# baseboard.net
KiCad netlist of a schematic drawn in Altium Designer
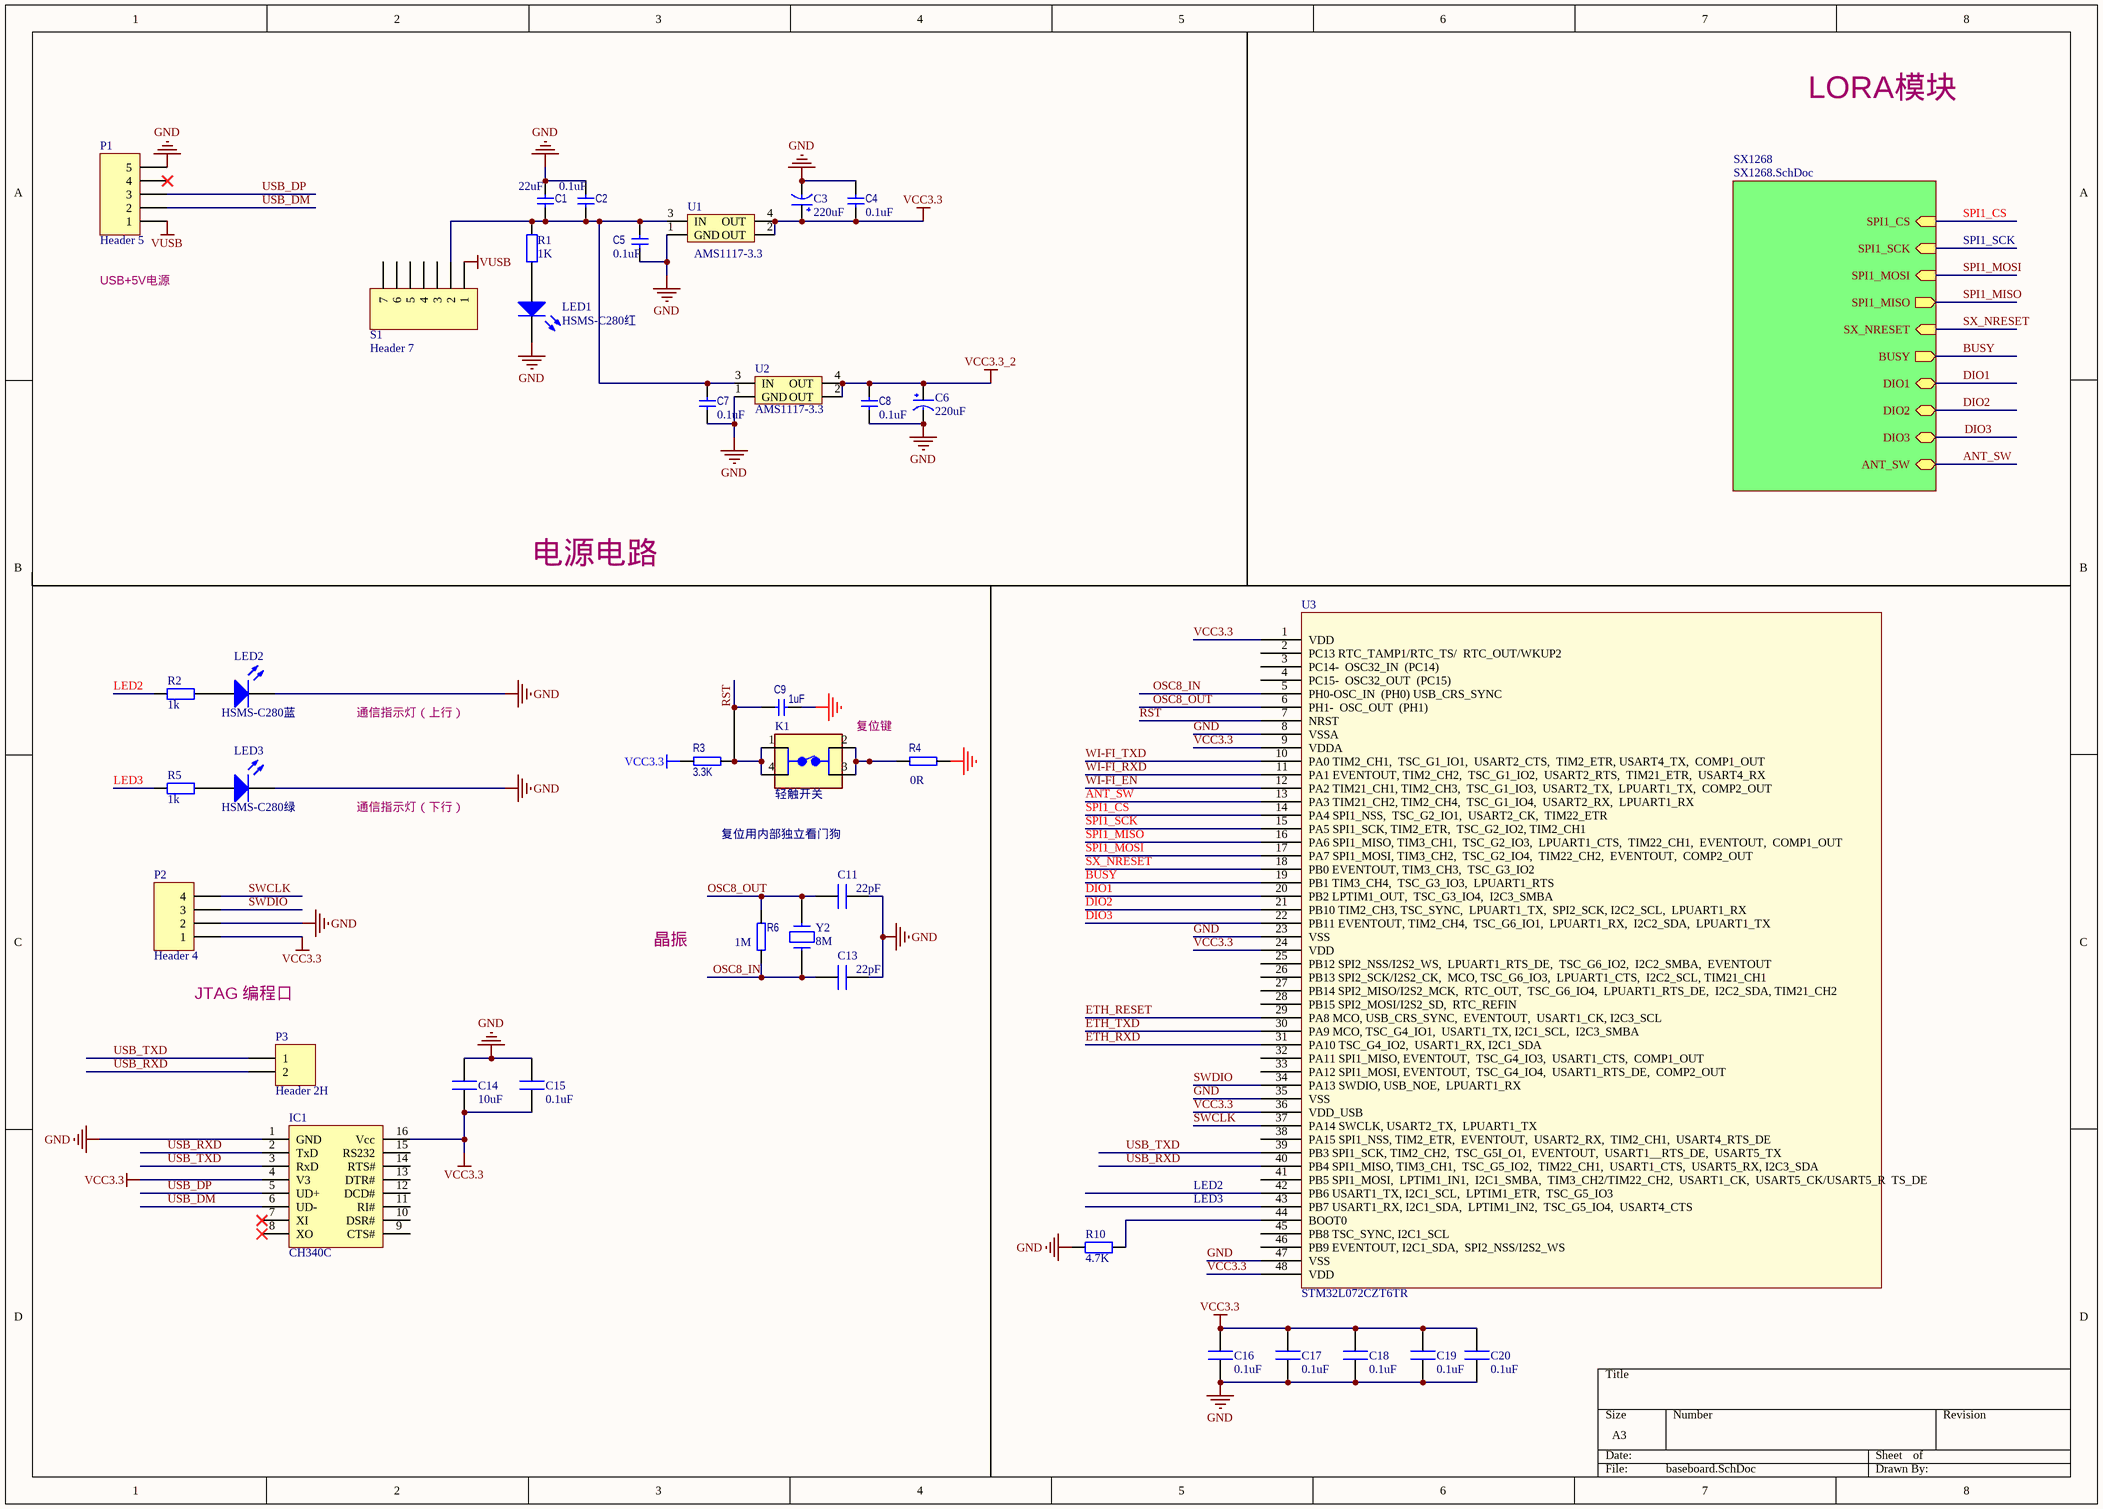
[diagram p0: baseboard.SchDoc]

(export (version "E")
  (design (tool "Eeschema 10.0.6"))
  (components
    (comp (ref "C1")
      (value "22uF")
      (footprint "C 0603_M")
      (libsource (lib "baseboard") (part "ProE.tmp_22p_13"))
    )
    (comp (ref "C2")
      (value "0.1uF")
      (footprint "C 0603_M")
      (libsource (lib "baseboard") (part "ProE.tmp_22p_13"))
    )
    (comp (ref "C3") (value "220uF") (footprint "CC6.56.5") (libsource (lib "baseboard") (part "CAP_1")))
    (comp (ref "C4")
      (value "0.1uF")
      (footprint "C 0603_M")
      (libsource (lib "baseboard") (part "ProE.tmp_22p_13"))
    )
    (comp (ref "C5")
      (value "0.1uF")
      (footprint "C 0603_M")
      (libsource (lib "baseboard") (part "ProE.tmp_22p_13"))
    )
    (comp (ref "C6") (value "220uF") (footprint "CC6.56.5") (libsource (lib "") (part "CAP_1_1")))
    (comp (ref "C7")
      (value "0.1uF")
      (footprint "C 0603_M")
      (libsource (lib "baseboard") (part "ProE.tmp_22p_13"))
    )
    (comp (ref "C8")
      (value "0.1uF")
      (footprint "C 0603_M")
      (libsource (lib "baseboard") (part "ProE.tmp_22p_13"))
    )
    (comp (ref "C9")
      (value "1uF")
      (footprint "C 0603_M")
      (libsource (lib "baseboard") (part "ProE.tmp_22p_13"))
    )
    (comp (ref "C11")
      (value "22pF")
      (footprint "C 0603_M")
      (description "Capacitor")
      (libsource (lib "Liuzhx") (part "普通贴片电容"))
    )
    (comp (ref "C13")
      (value "22pF")
      (footprint "C 0603_M")
      (description "Capacitor")
      (libsource (lib "Liuzhx") (part "普通贴片电容"))
    )
    (comp (ref "C14")
      (value "10uF")
      (footprint "C 0603_M")
      (description "Capacitor")
      (libsource (lib "Liuzhx") (part "普通贴片电容"))
    )
    (comp (ref "C15")
      (value "0.1uF")
      (footprint "C 0603_M")
      (description "Capacitor")
      (libsource (lib "Liuzhx") (part "普通贴片电容"))
    )
    (comp (ref "C16")
      (value "0.1uF")
      (footprint "C 0603_M")
      (description "Capacitor")
      (libsource (lib "Liuzhx") (part "普通贴片电容"))
    )
    (comp (ref "C17")
      (value "0.1uF")
      (footprint "C 0603_M")
      (description "Capacitor")
      (libsource (lib "Liuzhx") (part "普通贴片电容"))
    )
    (comp (ref "C18")
      (value "0.1uF")
      (footprint "C 0603_M")
      (description "Capacitor")
      (libsource (lib "Liuzhx") (part "普通贴片电容"))
    )
    (comp (ref "C19")
      (value "0.1uF")
      (footprint "C 0603_M")
      (description "Capacitor")
      (libsource (lib "Liuzhx") (part "普通贴片电容"))
    )
    (comp (ref "C20")
      (value "0.1uF")
      (footprint "C 0603_M")
      (description "Capacitor")
      (libsource (lib "Liuzhx") (part "普通贴片电容"))
    )
    (comp (ref "IC1")
      (value "CH340C")
      (footprint "SOP16_M")
      (description "串口转USB")
      (fields (field (name "版权归属") "源创客"))
      (libsource (lib "baseboard") (part "CH340G"))
    )
    (comp (ref "K1") (value "轻触开关") (footprint "SW4SM-4R5X4R5") (libsource (lib "baseboard") (part "轻触开关")))
    (comp (ref "LED1")
      (value "HSMS-C280红")
      (footprint "LED_DIP_1")
      (description "Miniature Chip LED, Red")
      (fields (field (name "PUBLISHER") "Altium Limited"))
      (libsource (lib "Agilent Optoelectronic LED") (part "HSMS-C280"))
    )
    (comp (ref "LED2")
      (value "HSMS-C280蓝")
      (footprint "LED_DIP_1")
      (description "Miniature Chip LED, Red")
      (fields (field (name "PUBLISHER") "Altium Limited"))
      (libsource (lib "Agilent Optoelectronic LED") (part "HSMS-C280"))
    )
    (comp (ref "LED3")
      (value "HSMS-C280绿")
      (footprint "LED_DIP_1")
      (description "Miniature Chip LED, Red")
      (fields (field (name "PUBLISHER") "Altium Limited"))
      (libsource (lib "Agilent Optoelectronic LED") (part "HSMS-C280"))
    )
    (comp (ref "P1")
      (value "Header 5")
      (footprint "USB-MICRO_D")
      (description "Header, 5-Pin")
      (fields (field (name "PUBLISHER") "Altium Limited"))
      (libsource (lib "Miscellaneous Connectors") (part "Header 5"))
    )
    (comp (ref "P2")
      (value "Header 4")
      (footprint "HDR1X4")
      (description "Header, 4-Pin")
      (fields (field (name "PUBLISHER") "Altium Limited"))
      (libsource (lib "Miscellaneous Connectors") (part "Header 4"))
    )
    (comp (ref "P3")
      (value "Header 2H")
      (footprint "HDR2.54-LI-2P")
      (description "Header, 2-Pin, Right Angle")
      (fields (field (name "PUBLISHER") "Altium Limited"))
      (libsource (lib "baseboard") (part "Header 2H"))
    )
    (comp (ref "R1")
      (value "1K")
      (footprint "0603R")
      (description "Resistor")
      (fields (field (name "PUBLISHER") "Altium Limited"))
      (libsource (lib "Miscellaneous Devices") (part "Res2"))
    )
    (comp (ref "R2")
      (value "1k")
      (footprint "0603R")
      (description "Resistor SMD - IEC symbol version")
      (libsource (lib "SX1276_e268v01a") (part "Resistor"))
    )
    (comp (ref "R3")
      (value "3.3K")
      (footprint "0603R")
      (libsource (lib "baseboard") (part "ProE.tmp_10k_66"))
    )
    (comp (ref "R4") (value "0R") (footprint "0603R") (libsource (lib "baseboard") (part "ProE.tmp_10k_66")))
    (comp (ref "R5")
      (value "1k")
      (footprint "0603R")
      (description "Resistor SMD - IEC symbol version")
      (libsource (lib "SX1276_e268v01a") (part "Resistor"))
    )
    (comp (ref "R6") (value "1M") (footprint "0603R") (libsource (lib "baseboard") (part "ProE.tmp_10k_66")))
    (comp (ref "R10")
      (value "4.7K")
      (footprint "0603R")
      (description "Resistor SMD - IEC symbol version")
      (libsource (lib "SX1276_e268v01a") (part "Resistor"))
    )
    (comp (ref "S1")
      (value "Header 7")
      (footprint "7脚3档开关")
      (description "Header, 7-Pin")
      (fields (field (name "PUBLISHER") "Altium Limited"))
      (libsource (lib "Miscellaneous Connectors") (part "Header 7"))
    )
    (comp (ref "U1")
      (value "AMS1117-3.3")
      (footprint "AMS1117")
      (libsource (lib "baseboard") (part "AMS1117"))
    )
    (comp (ref "U2")
      (value "AMS1117-3.3")
      (footprint "AMS1117")
      (libsource (lib "baseboard") (part "AMS1117"))
    )
    (comp (ref "U3")
      (value "STM32L072CZT6TR")
      (footprint "LQFP48_L")
      (libsource (lib "baseboard") (part "STM32L072CZT6TR"))
    )
    (comp (ref "Y2")
      (value "8M")
      (footprint "OSC3225")
      (description "Crystal")
      (libsource (lib "Liuzhx") (part "CRYSTAL"))
    )
  )
  (nets
    (net (code "1") (name "/ANT_SW") (class "Default")
      (node (ref "U3") (pin "13") (pinfunction "PA3_TIM21_CH2,_TIM2_CH4,__TSC_G1_IO4,__USART2_RX,__LPUART1_RX_13") (pintype "passive"))
    )
    (net (code "2") (name "/BUSY") (class "Default")
      (node (ref "U3") (pin "19") (pinfunction "PB1_TIM3_CH4,__TSC_G3_IO3,__LPUART1_RTS_19") (pintype "passive"))
    )
    (net (code "3") (name "/DIO1") (class "Default")
      (node (ref "U3") (pin "20") (pinfunction "PB2_LPTIM1_OUT,__TSC_G3_IO4,__I2C3_SMBA_20") (pintype "passive"))
    )
    (net (code "4") (name "/DIO2") (class "Default")
      (node (ref "U3") (pin "21") (pinfunction "PB10_TIM2_CH3,_TSC_SYNC,__LPUART1_TX,__SPI2_SCK,_I2C2_SCL,__LPUART1_RX_21") (pintype "passive"))
    )
    (net (code "5") (name "/DIO3") (class "Default")
      (node (ref "U3") (pin "22") (pinfunction "PB11_EVENTOUT,_TIM2_CH4,__TSC_G6_IO1,__LPUART1_RX,__I2C2_SDA,__LPUART1_TX_22") (pintype "passive"))
    )
    (net (code "6") (name "/ETH_RESET") (class "Default")
      (node (ref "U3") (pin "29") (pinfunction "PA8_MCO,_USB_CRS_SYNC,__EVENTOUT,__USART1_CK,_I2C3_SCL_29") (pintype "passive"))
    )
    (net (code "7") (name "/ETH_RXD") (class "Default")
      (node (ref "U3") (pin "31") (pinfunction "PA10_TSC_G4_IO2,__USART1_RX,_I2C1_SDA_31") (pintype "passive"))
    )
    (net (code "8") (name "/ETH_TXD") (class "Default")
      (node (ref "U3") (pin "30") (pinfunction "PA9_MCO,_TSC_G4_IO1,__USART1_TX,_I2C1_SCL,__I2C3_SMBA_30") (pintype "passive"))
    )
    (net (code "9") (name "/LED2") (class "Default")
      (node (ref "R2") (pin "1") (pinfunction "1_1") (pintype "passive"))
      (node (ref "U3") (pin "42") (pinfunction "PB6_USART1_TX,_I2C1_SCL,__LPTIM1_ETR,__TSC_G5_IO3_42") (pintype "passive"))
    )
    (net (code "10") (name "/LED3") (class "Default")
      (node (ref "R5") (pin "1") (pinfunction "1_1") (pintype "passive"))
      (node (ref "U3") (pin "43") (pinfunction "PB7_USART1_RX,_I2C1_SDA,__LPTIM1_IN2,__TSC_G5_IO4,__USART4_CTS_43") (pintype "passive"))
    )
    (net (code "11") (name "/OSC8_IN") (class "Default")
      (node (ref "C13") (pin "1") (pinfunction "1_1") (pintype "passive"))
      (node (ref "R6") (pin "2") (pintype "passive"))
      (node (ref "U3") (pin "5") (pinfunction "PH0-OSC_IN__(PH0)_USB_CRS_SYNC_5") (pintype "passive"))
      (node (ref "Y2") (pin "2") (pinfunction "2_2") (pintype "passive"))
    )
    (net (code "12") (name "/OSC8_OUT") (class "Default")
      (node (ref "C11") (pin "1") (pinfunction "1_1") (pintype "passive"))
      (node (ref "R6") (pin "1") (pintype "passive"))
      (node (ref "U3") (pin "6") (pinfunction "PH1-__OSC_OUT__(PH1)_6") (pintype "passive"))
      (node (ref "Y2") (pin "1") (pinfunction "1_1") (pintype "passive"))
    )
    (net (code "13") (name "/RST") (class "Default")
      (node (ref "C9") (pin "1") (pintype "passive"))
      (node (ref "K1") (pin "1") (pinfunction "1_1") (pintype "passive"))
      (node (ref "K1") (pin "4") (pinfunction "4_4") (pintype "passive"))
      (node (ref "R3") (pin "2") (pintype "passive"))
      (node (ref "U3") (pin "7") (pinfunction "NRST_7") (pintype "passive"))
    )
    (net (code "14") (name "/SPI1_CS") (class "Default")
      (node (ref "U3") (pin "14") (pinfunction "PA4_SPI1_NSS,__TSC_G2_IO1,__USART2_CK,__TIM22_ETR_14") (pintype "passive"))
    )
    (net (code "15") (name "/SPI1_MISO") (class "Default")
      (node (ref "U3") (pin "16") (pinfunction "PA6_SPI1_MISO,_TIM3_CH1,__TSC_G2_IO3,__LPUART1_CTS,__TIM22_CH1,__EVENTOUT,__COMP1_OUT_16") (pintype "passive"))
    )
    (net (code "16") (name "/SPI1_MOSI") (class "Default")
      (node (ref "U3") (pin "17") (pinfunction "PA7_SPI1_MOSI,_TIM3_CH2,__TSC_G2_IO4,__TIM22_CH2,__EVENTOUT,__COMP2_OUT_17") (pintype "passive"))
    )
    (net (code "17") (name "/SPI1_SCK") (class "Default")
      (node (ref "U3") (pin "15") (pinfunction "PA5_SPI1_SCK,_TIM2_ETR,__TSC_G2_IO2,_TIM2_CH1_15") (pintype "passive"))
    )
    (net (code "18") (name "/SWCLK") (class "Default")
      (node (ref "P2") (pin "4") (pinfunction "4_4") (pintype "passive"))
      (node (ref "U3") (pin "37") (pinfunction "PA14_SWCLK,_USART2_TX,__LPUART1_TX_37") (pintype "passive"))
    )
    (net (code "19") (name "/SWDIO") (class "Default")
      (node (ref "P2") (pin "3") (pinfunction "3_3") (pintype "passive"))
      (node (ref "U3") (pin "34") (pinfunction "PA13_SWDIO,_USB_NOE,__LPUART1_RX_34") (pintype "passive"))
    )
    (net (code "20") (name "/SX_NRESET") (class "Default")
      (node (ref "U3") (pin "18") (pinfunction "PB0_EVENTOUT,_TIM3_CH3,__TSC_G3_IO2_18") (pintype "passive"))
    )
    (net (code "21") (name "/USB_DM") (class "Default")
      (node (ref "IC1") (pin "6") (pinfunction "UD-_6") (pintype "passive"))
      (node (ref "P1") (pin "2") (pinfunction "2_2") (pintype "passive"))
    )
    (net (code "22") (name "/USB_DP") (class "Default")
      (node (ref "IC1") (pin "5") (pinfunction "UD+_5") (pintype "passive"))
      (node (ref "P1") (pin "3") (pinfunction "3_3") (pintype "passive"))
    )
    (net (code "23") (name "/USB_RXD") (class "Default")
      (node (ref "IC1") (pin "2") (pinfunction "TxD_2") (pintype "passive"))
      (node (ref "P3") (pin "2") (pinfunction "2_2") (pintype "passive"))
      (node (ref "U3") (pin "40") (pinfunction "PB4_SPI1_MISO,_TIM3_CH1,__TSC_G5_IO2,__TIM22_CH1,__USART1_CTS,__USART5_RX,_I2C3_SDA_40") (pintype "passive"))
    )
    (net (code "24") (name "/USB_TXD") (class "Default")
      (node (ref "IC1") (pin "3") (pinfunction "RxD_3") (pintype "passive"))
      (node (ref "P3") (pin "1") (pinfunction "1_1") (pintype "passive"))
      (node (ref "U3") (pin "39") (pinfunction "PB3_SPI1_SCK,_TIM2_CH2,__TSC_G5I_O1,__EVENTOUT,__USART1__RTS_DE,__USART5_TX_39") (pintype "passive"))
    )
    (net (code "25") (name "/WI-FI_EN") (class "Default")
      (node (ref "U3") (pin "12") (pinfunction "PA2_TIM21_CH1,_TIM2_CH3,__TSC_G1_IO3,__USART2_TX,__LPUART1_TX,__COMP2_OUT_12") (pintype "passive"))
    )
    (net (code "26") (name "/WI-FI_RXD") (class "Default")
      (node (ref "U3") (pin "11") (pinfunction "PA1_EVENTOUT,_TIM2_CH2,__TSC_G1_IO2,__USART2_RTS,__TIM21_ETR,__USART4_RX_11") (pintype "passive"))
    )
    (net (code "27") (name "/WI-FI_TXD") (class "Default")
      (node (ref "U3") (pin "10") (pinfunction "PA0_TIM2_CH1,__TSC_G1_IO1,__USART2_CTS,__TIM2_ETR,_USART4_TX,__COMP1_OUT_10") (pintype "passive"))
    )
    (net (code "28") (name "GND") (class "Default")
      (node (ref "C1") (pin "1") (pintype "passive"))
      (node (ref "C11") (pin "2") (pinfunction "2_2") (pintype "passive"))
      (node (ref "C13") (pin "2") (pinfunction "2_2") (pintype "passive"))
      (node (ref "C14") (pin "1") (pinfunction "1_1") (pintype "passive"))
      (node (ref "C15") (pin "2") (pinfunction "2_2") (pintype "passive"))
      (node (ref "C16") (pin "1") (pinfunction "1_1") (pintype "passive"))
      (node (ref "C17") (pin "1") (pinfunction "1_1") (pintype "passive"))
      (node (ref "C18") (pin "1") (pinfunction "1_1") (pintype "passive"))
      (node (ref "C19") (pin "1") (pinfunction "1_1") (pintype "passive"))
      (node (ref "C2") (pin "1") (pintype "passive"))
      (node (ref "C20") (pin "1") (pinfunction "1_1") (pintype "passive"))
      (node (ref "C3") (pin "2") (pinfunction "GND_2") (pintype "passive"))
      (node (ref "C4") (pin "2") (pintype "passive"))
      (node (ref "C5") (pin "1") (pintype "passive"))
      (node (ref "C6") (pin "2") (pinfunction "GND_2") (pintype "passive"))
      (node (ref "C7") (pin "1") (pintype "passive"))
      (node (ref "C8") (pin "2") (pintype "passive"))
      (node (ref "C9") (pin "2") (pintype "passive"))
      (node (ref "IC1") (pin "1") (pinfunction "GND_1") (pintype "passive"))
      (node (ref "LED1") (pin "2") (pinfunction "K_2") (pintype "passive"))
      (node (ref "LED2") (pin "2") (pinfunction "K_2") (pintype "passive"))
      (node (ref "LED3") (pin "2") (pinfunction "K_2") (pintype "passive"))
      (node (ref "P1") (pin "5") (pinfunction "5_5") (pintype "passive"))
      (node (ref "P2") (pin "2") (pinfunction "2_2") (pintype "passive"))
      (node (ref "R10") (pin "1") (pinfunction "1_1") (pintype "passive"))
      (node (ref "R4") (pin "2") (pintype "passive"))
      (node (ref "U1") (pin "1") (pinfunction "GND_1") (pintype "passive"))
      (node (ref "U2") (pin "1") (pinfunction "GND_1") (pintype "passive"))
      (node (ref "U3") (pin "23") (pinfunction "VSS_23") (pintype "passive"))
      (node (ref "U3") (pin "35") (pinfunction "VSS_35") (pintype "passive"))
      (node (ref "U3") (pin "47") (pinfunction "VSS_47") (pintype "passive"))
      (node (ref "U3") (pin "8") (pinfunction "VSSA_8") (pintype "passive"))
    )
    (net (code "29") (name "Net-(K1-Pad2)") (class "Default")
      (node (ref "K1") (pin "2") (pinfunction "2_2") (pintype "passive"))
      (node (ref "K1") (pin "3") (pinfunction "3_3") (pintype "passive"))
      (node (ref "R4") (pin "1") (pintype "passive"))
    )
    (net (code "30") (name "Net-(LED1-A)") (class "Default")
      (node (ref "LED1") (pin "1") (pinfunction "A_1") (pintype "passive"))
      (node (ref "R1") (pin "1") (pinfunction "1_1") (pintype "passive"))
    )
    (net (code "31") (name "Net-(LED2-A)") (class "Default")
      (node (ref "LED2") (pin "1") (pinfunction "A_1") (pintype "passive"))
      (node (ref "R2") (pin "2") (pinfunction "2_2") (pintype "passive"))
    )
    (net (code "32") (name "Net-(LED3-A)") (class "Default")
      (node (ref "LED3") (pin "1") (pinfunction "A_1") (pintype "passive"))
      (node (ref "R5") (pin "2") (pinfunction "2_2") (pintype "passive"))
    )
    (net (code "33") (name "Net-(U1-IN)") (class "Default")
      (node (ref "C1") (pin "2") (pintype "passive"))
      (node (ref "C2") (pin "2") (pintype "passive"))
      (node (ref "C5") (pin "2") (pintype "passive"))
      (node (ref "C7") (pin "2") (pintype "passive"))
      (node (ref "R1") (pin "2") (pinfunction "2_2") (pintype "passive"))
      (node (ref "S1") (pin "2") (pinfunction "2_2") (pintype "passive"))
      (node (ref "U1") (pin "3") (pinfunction "IN_3") (pintype "passive"))
      (node (ref "U2") (pin "3") (pinfunction "IN_3") (pintype "passive"))
    )
    (net (code "34") (name "Net-(U3-BOOT0)") (class "Default")
      (node (ref "R10") (pin "2") (pinfunction "2_2") (pintype "passive"))
      (node (ref "U3") (pin "44") (pinfunction "BOOT0_44") (pintype "passive"))
    )
    (net (code "35") (name "VCC3.3") (class "Default")
      (node (ref "C14") (pin "2") (pinfunction "2_2") (pintype "passive"))
      (node (ref "C15") (pin "1") (pinfunction "1_1") (pintype "passive"))
      (node (ref "C16") (pin "2") (pinfunction "2_2") (pintype "passive"))
      (node (ref "C17") (pin "2") (pinfunction "2_2") (pintype "passive"))
      (node (ref "C18") (pin "2") (pinfunction "2_2") (pintype "passive"))
      (node (ref "C19") (pin "2") (pinfunction "2_2") (pintype "passive"))
      (node (ref "C20") (pin "2") (pinfunction "2_2") (pintype "passive"))
      (node (ref "C3") (pin "1") (pinfunction "VCC_1") (pintype "passive"))
      (node (ref "C4") (pin "1") (pintype "passive"))
      (node (ref "IC1") (pin "16") (pinfunction "Vcc_16") (pintype "passive"))
      (node (ref "IC1") (pin "4") (pinfunction "V3_4") (pintype "passive"))
      (node (ref "P2") (pin "1") (pinfunction "1_1") (pintype "passive"))
      (node (ref "R3") (pin "1") (pintype "passive"))
      (node (ref "U1") (pin "2") (pinfunction "OUT_2") (pintype "passive"))
      (node (ref "U1") (pin "4") (pinfunction "OUT_4") (pintype "passive"))
      (node (ref "U3") (pin "1") (pinfunction "VDD_1") (pintype "passive"))
      (node (ref "U3") (pin "24") (pinfunction "VDD_24") (pintype "passive"))
      (node (ref "U3") (pin "36") (pinfunction "VDD_USB_36") (pintype "passive"))
      (node (ref "U3") (pin "48") (pinfunction "VDD_48") (pintype "passive"))
      (node (ref "U3") (pin "9") (pinfunction "VDDA_9") (pintype "passive"))
    )
    (net (code "36") (name "VCC3.3_2") (class "Default")
      (node (ref "C6") (pin "1") (pinfunction "VCC_1") (pintype "passive"))
      (node (ref "C8") (pin "1") (pintype "passive"))
      (node (ref "U2") (pin "2") (pinfunction "OUT_2") (pintype "passive"))
      (node (ref "U2") (pin "4") (pinfunction "OUT_4") (pintype "passive"))
    )
    (net (code "37") (name "VUSB") (class "Default")
      (node (ref "P1") (pin "1") (pinfunction "1_1") (pintype "passive"))
      (node (ref "S1") (pin "1") (pinfunction "1_1") (pintype "passive"))
    )
    (net (code "38") (name "unconnected-(IC1-CTS#-Pad9)") (class "Default")
      (node (ref "IC1") (pin "9") (pinfunction "CTS#_9") (pintype "passive"))
    )
    (net (code "39") (name "unconnected-(IC1-DCD#-Pad12)") (class "Default")
      (node (ref "IC1") (pin "12") (pinfunction "DCD#_12") (pintype "passive"))
    )
    (net (code "40") (name "unconnected-(IC1-DSR#-Pad10)") (class "Default")
      (node (ref "IC1") (pin "10") (pinfunction "DSR#_10") (pintype "passive"))
    )
    (net (code "41") (name "unconnected-(IC1-DTR#-Pad13)") (class "Default")
      (node (ref "IC1") (pin "13") (pinfunction "DTR#_13") (pintype "passive"))
    )
    (net (code "42") (name "unconnected-(IC1-RI#-Pad11)") (class "Default")
      (node (ref "IC1") (pin "11") (pinfunction "RI#_11") (pintype "passive"))
    )
    (net (code "43") (name "unconnected-(IC1-RS232-Pad15)") (class "Default")
      (node (ref "IC1") (pin "15") (pinfunction "RS232_15") (pintype "passive"))
    )
    (net (code "44") (name "unconnected-(IC1-RTS#-Pad14)") (class "Default")
      (node (ref "IC1") (pin "14") (pinfunction "RTS#_14") (pintype "passive"))
    )
    (net (code "45") (name "unconnected-(IC1-XI-Pad7)") (class "Default")
      (node (ref "IC1") (pin "7") (pinfunction "XI_7") (pintype "passive+no_connect"))
    )
    (net (code "46") (name "unconnected-(IC1-XO-Pad8)") (class "Default")
      (node (ref "IC1") (pin "8") (pinfunction "XO_8") (pintype "passive+no_connect"))
    )
    (net (code "47") (name "unconnected-(P1-Pad4)") (class "Default")
      (node (ref "P1") (pin "4") (pinfunction "4_4") (pintype "passive+no_connect"))
    )
    (net (code "48") (name "unconnected-(S1-Pad3)") (class "Default")
      (node (ref "S1") (pin "3") (pinfunction "3_3") (pintype "passive"))
    )
    (net (code "49") (name "unconnected-(S1-Pad4)") (class "Default")
      (node (ref "S1") (pin "4") (pinfunction "4_4") (pintype "passive"))
    )
    (net (code "50") (name "unconnected-(S1-Pad5)") (class "Default")
      (node (ref "S1") (pin "5") (pinfunction "5_5") (pintype "passive"))
    )
    (net (code "51") (name "unconnected-(S1-Pad6)") (class "Default")
      (node (ref "S1") (pin "6") (pinfunction "6_6") (pintype "passive"))
    )
    (net (code "52") (name "unconnected-(S1-Pad7)") (class "Default")
      (node (ref "S1") (pin "7") (pinfunction "7_7") (pintype "passive"))
    )
    (net (code "53") (name "unconnected-(U3-PA11_SPI1_MISO,_EVENTOUT,__TSC_G4_IO3,__USART1_CTS,__COMP1_OUT-Pad32)") (class "Default")
      (node (ref "U3") (pin "32") (pinfunction "PA11_SPI1_MISO,_EVENTOUT,__TSC_G4_IO3,__USART1_CTS,__COMP1_OUT_32") (pintype "passive"))
    )
    (net (code "54") (name "unconnected-(U3-PA12_SPI1_MOSI,_EVENTOUT,__TSC_G4_IO4,__USART1_RTS_DE,__COMP2_OUT-Pad33)") (class "Default")
      (node (ref "U3") (pin "33") (pinfunction "PA12_SPI1_MOSI,_EVENTOUT,__TSC_G4_IO4,__USART1_RTS_DE,__COMP2_OUT_33") (pintype "passive"))
    )
    (net (code "55") (name "unconnected-(U3-PA15_SPI1_NSS,_TIM2_ETR,__EVENTOUT,__USART2_RX,__TIM2_CH1,__USART4_RTS_DE-Pad38)") (class "Default")
      (node (ref "U3") (pin "38") (pinfunction "PA15_SPI1_NSS,_TIM2_ETR,__EVENTOUT,__USART2_RX,__TIM2_CH1,__USART4_RTS_DE_38") (pintype "passive"))
    )
    (net (code "56") (name "unconnected-(U3-PB5_SPI1_MOSI,__LPTIM1_IN1,__I2C1_SMBA,__TIM3_CH2{slash}TIM22_CH2,__USART1_CK,__USART5_CK{slash}USART5_R__TS_DE-Pad41)") (class "Default")
      (node (ref "U3") (pin "41") (pinfunction "PB5_SPI1_MOSI,__LPTIM1_IN1,__I2C1_SMBA,__TIM3_CH2/TIM22_CH2,__USART1_CK,__USART5_CK/USART5_R__TS_DE_41") (pintype "passive"))
    )
    (net (code "57") (name "unconnected-(U3-PB8_TSC_SYNC,_I2C1_SCL-Pad45)") (class "Default")
      (node (ref "U3") (pin "45") (pinfunction "PB8_TSC_SYNC,_I2C1_SCL_45") (pintype "passive"))
    )
    (net (code "58") (name "unconnected-(U3-PB9_EVENTOUT,_I2C1_SDA,__SPI2_NSS{slash}I2S2_WS-Pad46)") (class "Default")
      (node (ref "U3") (pin "46") (pinfunction "PB9_EVENTOUT,_I2C1_SDA,__SPI2_NSS/I2S2_WS_46") (pintype "passive"))
    )
    (net (code "59") (name "unconnected-(U3-PB12_SPI2_NSS{slash}I2S2_WS,__LPUART1_RTS_DE,__TSC_G6_IO2,__I2C2_SMBA,__EVENTOUT-Pad25)") (class "Default")
      (node (ref "U3") (pin "25") (pinfunction "PB12_SPI2_NSS/I2S2_WS,__LPUART1_RTS_DE,__TSC_G6_IO2,__I2C2_SMBA,__EVENTOUT_25") (pintype "passive"))
    )
    (net (code "60") (name "unconnected-(U3-PB13_SPI2_SCK{slash}I2S2_CK,__MCO,_TSC_G6_IO3,__LPUART1_CTS,__I2C2_SCL,_TIM21_CH1-Pad26)") (class "Default")
      (node (ref "U3") (pin "26") (pinfunction "PB13_SPI2_SCK/I2S2_CK,__MCO,_TSC_G6_IO3,__LPUART1_CTS,__I2C2_SCL,_TIM21_CH1_26") (pintype "passive"))
    )
    (net (code "61") (name "unconnected-(U3-PB14_SPI2_MISO{slash}I2S2_MCK,__RTC_OUT,__TSC_G6_IO4,__LPUART1_RTS_DE,__I2C2_SDA,_TIM21_CH2-Pad27)") (class "Default")
      (node (ref "U3") (pin "27") (pinfunction "PB14_SPI2_MISO/I2S2_MCK,__RTC_OUT,__TSC_G6_IO4,__LPUART1_RTS_DE,__I2C2_SDA,_TIM21_CH2_27") (pintype "passive"))
    )
    (net (code "62") (name "unconnected-(U3-PB15_SPI2_MOSI{slash}I2S2_SD,__RTC_REFIN-Pad28)") (class "Default")
      (node (ref "U3") (pin "28") (pinfunction "PB15_SPI2_MOSI/I2S2_SD,__RTC_REFIN_28") (pintype "passive"))
    )
    (net (code "63") (name "unconnected-(U3-PC13_RTC_TAMP1{slash}RTC_TS{slash}__RTC_OUT{slash}WKUP2-Pad2)") (class "Default")
      (node (ref "U3") (pin "2") (pinfunction "PC13_RTC_TAMP1/RTC_TS/__RTC_OUT/WKUP2_2") (pintype "passive"))
    )
    (net (code "64") (name "unconnected-(U3-PC14-__OSC32_IN__(PC14)-Pad3)") (class "Default")
      (node (ref "U3") (pin "3") (pinfunction "PC14-__OSC32_IN__(PC14)_3") (pintype "passive"))
    )
    (net (code "65") (name "unconnected-(U3-PC15-__OSC32_OUT__(PC15)-Pad4)") (class "Default")
      (node (ref "U3") (pin "4") (pinfunction "PC15-__OSC32_OUT__(PC15)_4") (pintype "passive"))
    )
  )
)
